# keysweeper_mem_sm.net
KiCad netlist of a schematic drawn in EAGLE
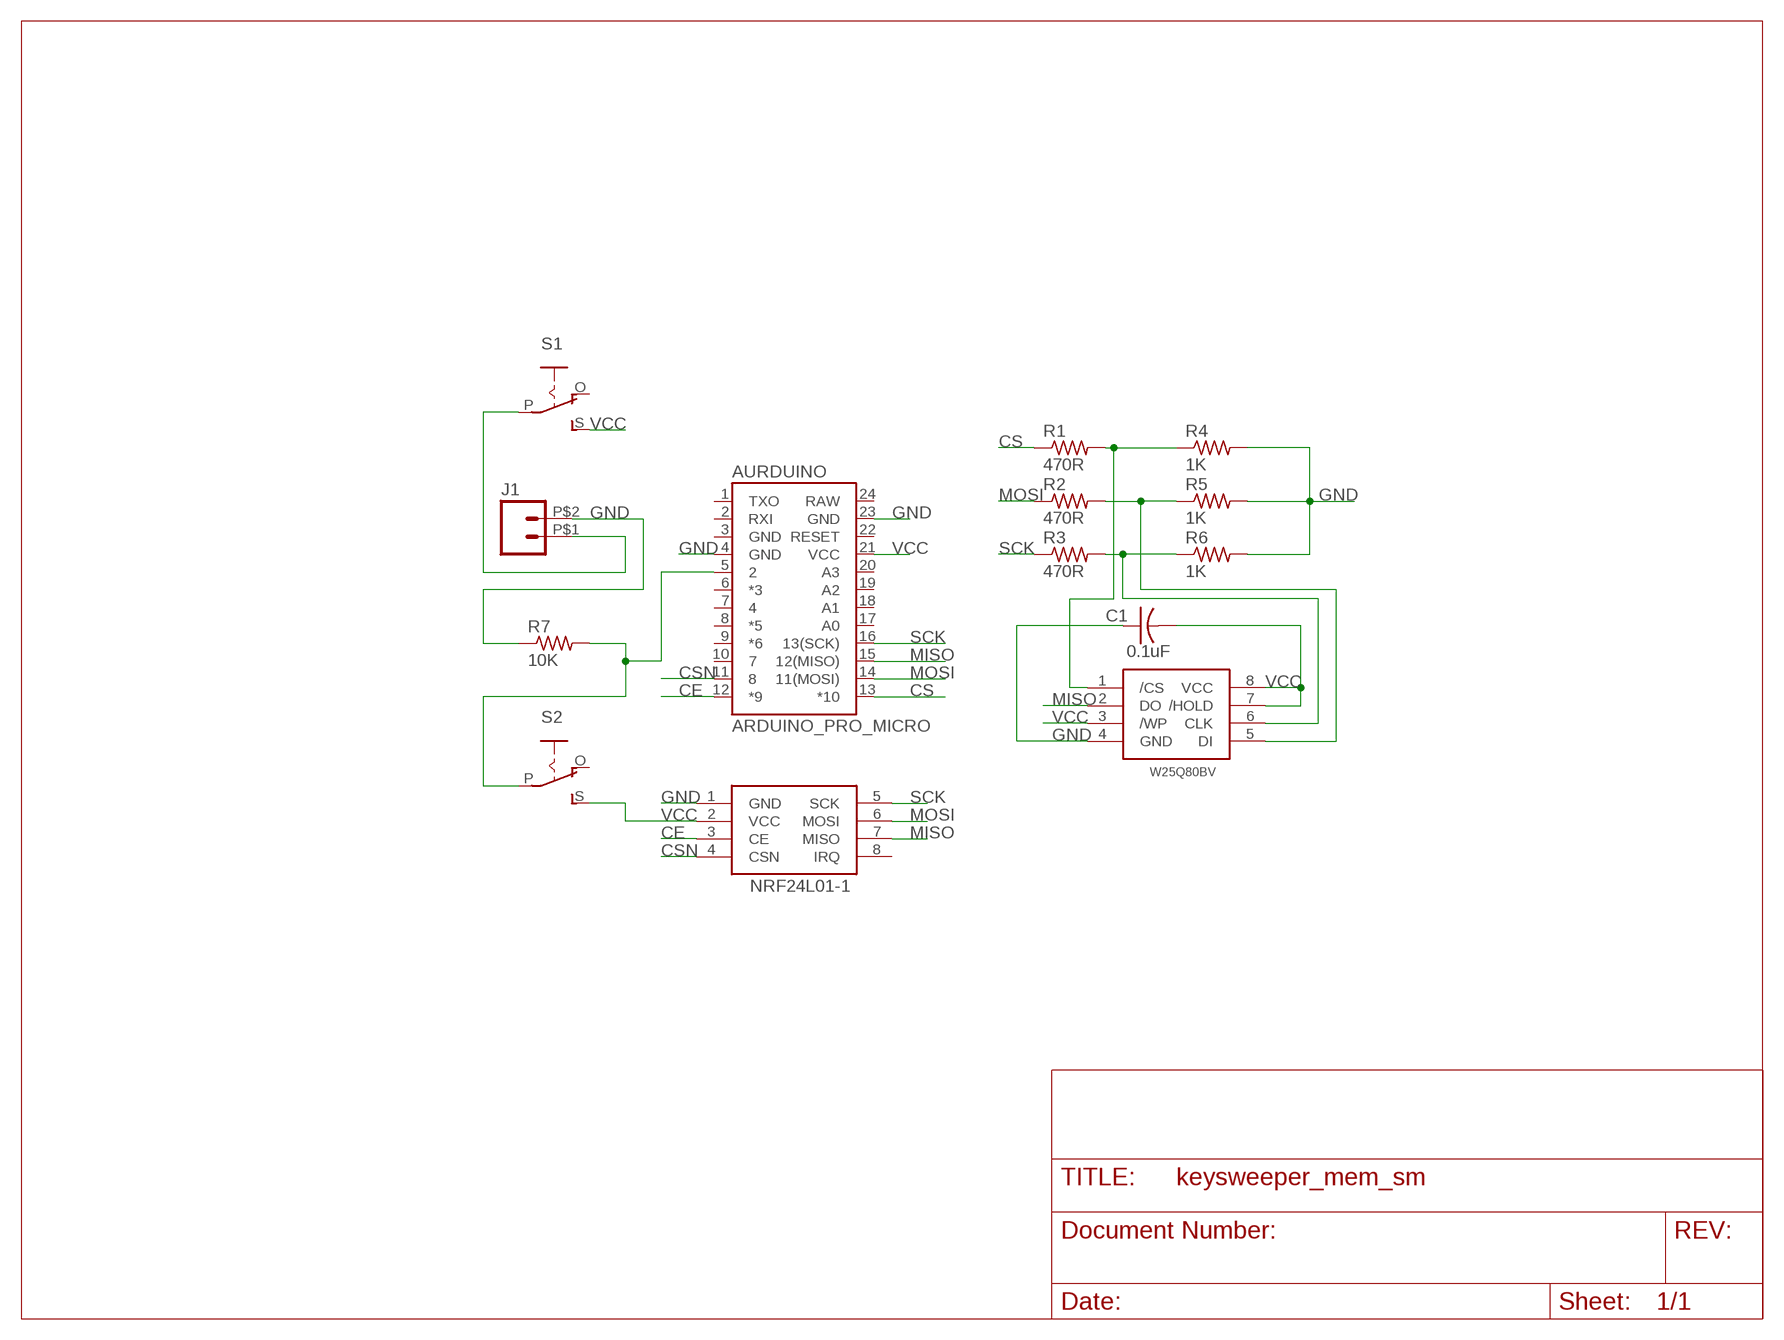
[diagram p0: schematic, sheet 1]

(export (version "E")
  (design (tool "Eeschema 10.0.6"))
  (components
    (comp (ref "AURDUINO")
      (value "ARDUINO_PRO_MICRO")
      (footprint "eagle-import:ARDUINO_PRO_MICRO")
      (libsource (lib "eagle-import") (part "ARDUINO_PRO_MICRO"))
    )
    (comp (ref "C1")
      (value "0.1uF")
      (footprint "eagle-import:C0805K")
      (libsource (lib "eagle-import") (part "C-USC0805K"))
    )
    (comp (ref "J1")
      (value "M02PTH2")
      (footprint "eagle-import:1X02_BIG")
      (libsource (lib "eagle-import") (part "M02PTH2"))
    )
    (comp (ref "R1")
      (value "470R")
      (footprint "eagle-import:R0805W")
      (libsource (lib "eagle-import") (part "R-US_R0805W"))
    )
    (comp (ref "R2")
      (value "470R")
      (footprint "eagle-import:R0805W")
      (libsource (lib "eagle-import") (part "R-US_R0805W"))
    )
    (comp (ref "R3")
      (value "470R")
      (footprint "eagle-import:R0805W")
      (libsource (lib "eagle-import") (part "R-US_R0805W"))
    )
    (comp (ref "R4")
      (value "1K")
      (footprint "eagle-import:R0805W")
      (libsource (lib "eagle-import") (part "R-US_R0805W"))
    )
    (comp (ref "R5")
      (value "1K")
      (footprint "eagle-import:R0805W")
      (libsource (lib "eagle-import") (part "R-US_R0805W"))
    )
    (comp (ref "R6")
      (value "1K")
      (footprint "eagle-import:R0805W")
      (libsource (lib "eagle-import") (part "R-US_R0805W"))
    )
    (comp (ref "R7")
      (value "10K")
      (footprint "eagle-import:R0805W")
      (libsource (lib "eagle-import") (part "R-US_R0805W"))
    )
    (comp (ref "S1")
      (value "EG1218S")
      (footprint "eagle-import:EG1218")
      (libsource (lib "eagle-import") (part "EG1218S"))
    )
    (comp (ref "S2")
      (value "EG1218S")
      (footprint "eagle-import:EG1218")
      (libsource (lib "eagle-import") (part "EG1218S"))
    )
    (comp (ref "U1")
      (value "NRF24L01-8PIN")
      (footprint "eagle-import:NRF24L01")
      (libsource (lib "eagle-import") (part "NRF24L01-8PIN"))
    )
    (comp (ref "U2")
      (value "W25Q80BV-SMD")
      (footprint "eagle-import:W25Q80BV-SMD")
      (libsource (lib "eagle-import") (part "W25Q80BV-SMD"))
    )
  )
  (nets
    (net (code "1") (name "/CE") (class "Default")
      (node (ref "AURDUINO") (pin "12") (pinfunction "*9_12") (pintype "bidirectional"))
      (node (ref "U1") (pin "3") (pinfunction "CE_3") (pintype "bidirectional"))
    )
    (net (code "2") (name "/CS") (class "Default")
      (node (ref "AURDUINO") (pin "13") (pinfunction "*10_13") (pintype "bidirectional"))
      (node (ref "R1") (pin "1") (pinfunction "1_1") (pintype "passive"))
    )
    (net (code "3") (name "/CSN") (class "Default")
      (node (ref "AURDUINO") (pin "11") (pinfunction "8_11") (pintype "bidirectional"))
      (node (ref "U1") (pin "4") (pinfunction "CSN_4") (pintype "bidirectional"))
    )
    (net (code "4") (name "/GND") (class "Default")
      (node (ref "AURDUINO") (pin "23") (pinfunction "GND_23") (pintype "bidirectional"))
      (node (ref "AURDUINO") (pin "4") (pinfunction "GND_4") (pintype "bidirectional"))
      (node (ref "C1") (pin "1") (pinfunction "1_1") (pintype "passive"))
      (node (ref "J1") (pin "P$2") (pinfunction "2_P$2") (pintype "passive"))
      (node (ref "R4") (pin "2") (pinfunction "2_2") (pintype "passive"))
      (node (ref "R5") (pin "2") (pinfunction "2_2") (pintype "passive"))
      (node (ref "R6") (pin "2") (pinfunction "2_2") (pintype "passive"))
      (node (ref "R7") (pin "1") (pinfunction "1_1") (pintype "passive"))
      (node (ref "U1") (pin "1") (pinfunction "GND_1") (pintype "passive"))
      (node (ref "U2") (pin "4") (pinfunction "GND_4") (pintype "passive"))
    )
    (net (code "5") (name "/MISO") (class "Default")
      (node (ref "AURDUINO") (pin "15") (pinfunction "12(MISO)_15") (pintype "bidirectional"))
      (node (ref "U1") (pin "7") (pinfunction "MISO_7") (pintype "bidirectional"))
      (node (ref "U2") (pin "2") (pinfunction "DO_2") (pintype "bidirectional"))
    )
    (net (code "6") (name "/MOSI") (class "Default")
      (node (ref "AURDUINO") (pin "14") (pinfunction "11(MOSI)_14") (pintype "bidirectional"))
      (node (ref "R2") (pin "1") (pinfunction "1_1") (pintype "passive"))
      (node (ref "U1") (pin "6") (pinfunction "MOSI_6") (pintype "bidirectional"))
    )
    (net (code "7") (name "/SCK") (class "Default")
      (node (ref "AURDUINO") (pin "16") (pinfunction "13(SCK)_16") (pintype "bidirectional"))
      (node (ref "R3") (pin "1") (pinfunction "1_1") (pintype "passive"))
      (node (ref "U1") (pin "5") (pinfunction "SCK_5") (pintype "bidirectional"))
    )
    (net (code "8") (name "/VCC") (class "Default")
      (node (ref "AURDUINO") (pin "21") (pinfunction "VCC_21") (pintype "bidirectional"))
      (node (ref "C1") (pin "2") (pinfunction "2_2") (pintype "passive"))
      (node (ref "S1") (pin "S") (pinfunction "S_S") (pintype "passive"))
      (node (ref "S2") (pin "S") (pinfunction "S_S") (pintype "passive"))
      (node (ref "U1") (pin "2") (pinfunction "VCC_2") (pintype "passive"))
      (node (ref "U2") (pin "3") (pinfunction "/WP_3") (pintype "bidirectional"))
      (node (ref "U2") (pin "7") (pinfunction "/HOLD_7") (pintype "bidirectional"))
      (node (ref "U2") (pin "8") (pinfunction "VCC_8") (pintype "passive"))
    )
    (net (code "9") (name "Net-(AURDUINO-2)") (class "Default")
      (node (ref "AURDUINO") (pin "5") (pinfunction "2_5") (pintype "bidirectional"))
      (node (ref "R7") (pin "2") (pinfunction "2_2") (pintype "passive"))
      (node (ref "S2") (pin "P") (pinfunction "P_P") (pintype "passive"))
    )
    (net (code "10") (name "Net-(J1-1)") (class "Default")
      (node (ref "J1") (pin "P$1") (pinfunction "1_P$1") (pintype "passive"))
      (node (ref "S1") (pin "P") (pinfunction "P_P") (pintype "passive"))
    )
    (net (code "11") (name "Net-(U2-CLK)") (class "Default")
      (node (ref "R3") (pin "2") (pinfunction "2_2") (pintype "passive"))
      (node (ref "R6") (pin "1") (pinfunction "1_1") (pintype "passive"))
      (node (ref "U2") (pin "6") (pinfunction "CLK_6") (pintype "passive"))
    )
    (net (code "12") (name "Net-(U2-DI)") (class "Default")
      (node (ref "R2") (pin "2") (pinfunction "2_2") (pintype "passive"))
      (node (ref "R5") (pin "1") (pinfunction "1_1") (pintype "passive"))
      (node (ref "U2") (pin "5") (pinfunction "DI_5") (pintype "bidirectional"))
    )
    (net (code "13") (name "Net-(U2-{slash}CS)") (class "Default")
      (node (ref "R1") (pin "2") (pinfunction "2_2") (pintype "passive"))
      (node (ref "R4") (pin "1") (pinfunction "1_1") (pintype "passive"))
      (node (ref "U2") (pin "1") (pinfunction "/CS_1") (pintype "input"))
    )
    (net (code "14") (name "unconnected-(AURDUINO-*3-Pad6)") (class "Default")
      (node (ref "AURDUINO") (pin "6") (pinfunction "*3_6") (pintype "bidirectional"))
    )
    (net (code "15") (name "unconnected-(AURDUINO-*5-Pad8)") (class "Default")
      (node (ref "AURDUINO") (pin "8") (pinfunction "*5_8") (pintype "bidirectional"))
    )
    (net (code "16") (name "unconnected-(AURDUINO-*6-Pad9)") (class "Default")
      (node (ref "AURDUINO") (pin "9") (pinfunction "*6_9") (pintype "bidirectional"))
    )
    (net (code "17") (name "unconnected-(AURDUINO-4-Pad7)") (class "Default")
      (node (ref "AURDUINO") (pin "7") (pinfunction "4_7") (pintype "bidirectional"))
    )
    (net (code "18") (name "unconnected-(AURDUINO-7-Pad10)") (class "Default")
      (node (ref "AURDUINO") (pin "10") (pinfunction "7_10") (pintype "bidirectional"))
    )
    (net (code "19") (name "unconnected-(AURDUINO-A0-Pad17)") (class "Default")
      (node (ref "AURDUINO") (pin "17") (pinfunction "A0_17") (pintype "bidirectional"))
    )
    (net (code "20") (name "unconnected-(AURDUINO-A1-Pad18)") (class "Default")
      (node (ref "AURDUINO") (pin "18") (pinfunction "A1_18") (pintype "bidirectional"))
    )
    (net (code "21") (name "unconnected-(AURDUINO-A2-Pad19)") (class "Default")
      (node (ref "AURDUINO") (pin "19") (pinfunction "A2_19") (pintype "bidirectional"))
    )
    (net (code "22") (name "unconnected-(AURDUINO-A3-Pad20)") (class "Default")
      (node (ref "AURDUINO") (pin "20") (pinfunction "A3_20") (pintype "bidirectional"))
    )
    (net (code "23") (name "unconnected-(AURDUINO-GND-Pad3)") (class "Default")
      (node (ref "AURDUINO") (pin "3") (pinfunction "GND_3") (pintype "bidirectional"))
    )
    (net (code "24") (name "unconnected-(AURDUINO-RAW-Pad24)") (class "Default")
      (node (ref "AURDUINO") (pin "24") (pinfunction "RAW_24") (pintype "bidirectional"))
    )
    (net (code "25") (name "unconnected-(AURDUINO-RESET-Pad22)") (class "Default")
      (node (ref "AURDUINO") (pin "22") (pinfunction "RESET_22") (pintype "bidirectional"))
    )
    (net (code "26") (name "unconnected-(AURDUINO-RXI-Pad2)") (class "Default")
      (node (ref "AURDUINO") (pin "2") (pinfunction "RXI_2") (pintype "bidirectional"))
    )
    (net (code "27") (name "unconnected-(AURDUINO-TXO-Pad1)") (class "Default")
      (node (ref "AURDUINO") (pin "1") (pinfunction "TXO_1") (pintype "bidirectional"))
    )
    (net (code "28") (name "unconnected-(S1-PadO)") (class "Default")
      (node (ref "S1") (pin "O") (pinfunction "O_O") (pintype "passive"))
    )
    (net (code "29") (name "unconnected-(S2-PadO)") (class "Default")
      (node (ref "S2") (pin "O") (pinfunction "O_O") (pintype "passive"))
    )
    (net (code "30") (name "unconnected-(U1-IRQ-Pad8)") (class "Default")
      (node (ref "U1") (pin "8") (pinfunction "IRQ_8") (pintype "passive"))
    )
  )
)
